# Pour_Over_1_Final.net
KiCad netlist of a schematic drawn in Altium Designer
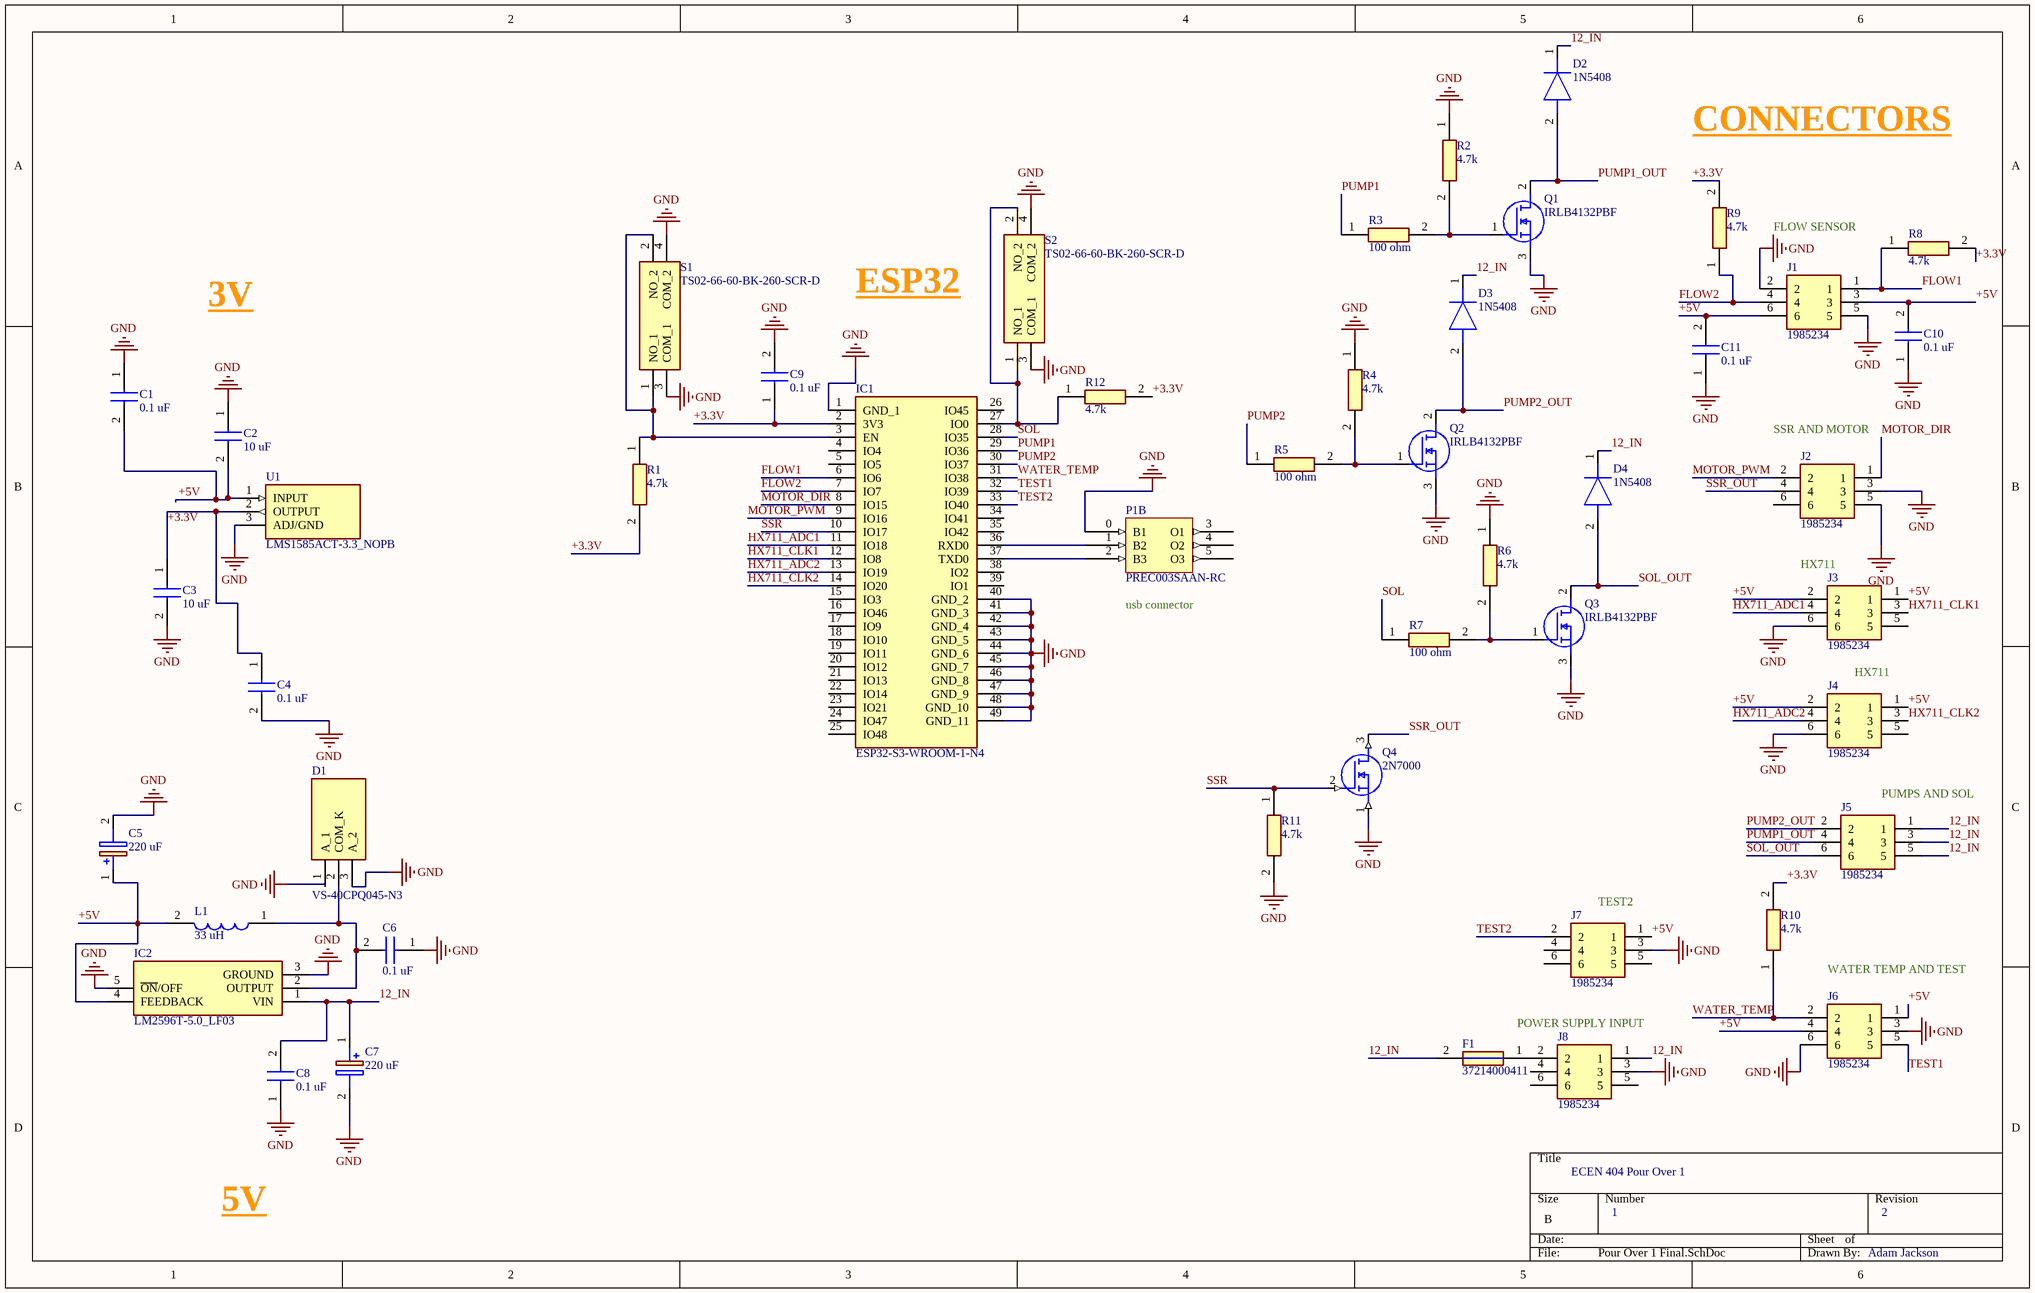
[diagram p0: Pour Over 1 Final.SchDoc]

(export (version "E")
  (design (tool "Eeschema 10.0.6"))
  (components
    (comp (ref "C1")
      (value "0.1 uF")
      (footprint "SamacSys:K104K10X7RF5TL2")
      (description "Capacitor")
      (fields
        (field (name "MANUFACTURER_PART_NUMBER") "K104K10X7RF5TL2")
        (field (name "MOUSER PART NUMBER") "594-K104K10X7RF5TL2")
      )
      (libsource (lib "*") (part "K104K10X7RF5TL2"))
    )
    (comp (ref "C2")
      (value "10 uF")
      (footprint "SamacSys:FG16")
      (description "Capacitor")
      (fields
        (field (name "MANUFACTURER_PART_NUMBER") "FG16X7R1E106KRT06")
        (field (name "MOUSER PART NUMBER") "810-FG16X7R1E106KRT6")
      )
      (libsource (lib "*") (part "FG16X7R1E106KRT06"))
    )
    (comp (ref "C3")
      (value "10 uF")
      (footprint "SamacSys:FG16")
      (description "Capacitor")
      (fields
        (field (name "MANUFACTURER_PART_NUMBER") "FG16X7R1E106KRT06")
        (field (name "MOUSER PART NUMBER") "810-FG16X7R1E106KRT6")
      )
      (libsource (lib "*") (part "FG16X7R1E106KRT06"))
    )
    (comp (ref "C4")
      (value "0.1 uF")
      (footprint "SamacSys:K104K10X7RF5TL2")
      (description "Capacitor")
      (fields
        (field (name "MANUFACTURER_PART_NUMBER") "K104K10X7RF5TL2")
        (field (name "MOUSER PART NUMBER") "594-K104K10X7RF5TL2")
      )
      (libsource (lib "*") (part "K104K10X7RF5TL2"))
    )
    (comp (ref "C5")
      (value "220 uF")
      (footprint "Footprints:EEHZT1E331UP")
      (description "Capacitor Polarised")
      (fields
        (field (name "MANUFACTURER_PART_NUMBER") "EEE-TP1C221AP")
        (field (name "MOUSER PART NUMBER") "667-EEE-TP1C221AP")
      )
      (libsource (lib "*") (part "EEE-TP1C221AP"))
    )
    (comp (ref "C6")
      (value "0.1 uF")
      (footprint "SamacSys:K104K10X7RF5TL2")
      (description "Capacitor")
      (fields
        (field (name "MANUFACTURER_PART_NUMBER") "K104K10X7RF5TL2")
        (field (name "MOUSER PART NUMBER") "594-K104K10X7RF5TL2")
      )
      (libsource (lib "*") (part "K104K10X7RF5TL2"))
    )
    (comp (ref "C7")
      (value "220 uF")
      (footprint "Footprints:EEHZT1E331UP")
      (description "Capacitor Polarised")
      (fields
        (field (name "MANUFACTURER_PART_NUMBER") "EEE-TP1C221AP")
        (field (name "MOUSER PART NUMBER") "667-EEE-TP1C221AP")
      )
      (libsource (lib "") (part "EEE-TP1C221AP_1"))
    )
    (comp (ref "C8")
      (value "0.1 uF")
      (footprint "SamacSys:K104K10X7RF5TL2")
      (description "Capacitor")
      (fields
        (field (name "MANUFACTURER_PART_NUMBER") "K104K10X7RF5TL2")
        (field (name "MOUSER PART NUMBER") "594-K104K10X7RF5TL2")
      )
      (libsource (lib "*") (part "K104K10X7RF5TL2"))
    )
    (comp (ref "C9")
      (value "0.1 uF")
      (footprint "SamacSys:K104K10X7RF5TL2")
      (description "Capacitor")
      (fields
        (field (name "MANUFACTURER_PART_NUMBER") "K104K10X7RF5TL2")
        (field (name "MOUSER PART NUMBER") "594-K104K10X7RF5TL2")
      )
      (libsource (lib "*") (part "K104K10X7RF5TL2"))
    )
    (comp (ref "C10")
      (value "0.1 uF")
      (footprint "SamacSys:K104K10X7RF5TL2")
      (description "Capacitor")
      (fields
        (field (name "MANUFACTURER_PART_NUMBER") "K104K10X7RF5TL2")
        (field (name "MOUSER PART NUMBER") "594-K104K10X7RF5TL2")
      )
      (libsource (lib "*") (part "K104K10X7RF5TL2"))
    )
    (comp (ref "C11")
      (value "0.1 uF")
      (footprint "SamacSys:K104K10X7RF5TL2")
      (description "Capacitor")
      (fields
        (field (name "MANUFACTURER_PART_NUMBER") "K104K10X7RF5TL2")
        (field (name "MOUSER PART NUMBER") "594-K104K10X7RF5TL2")
      )
      (libsource (lib "*") (part "K104K10X7RF5TL2"))
    )
    (comp (ref "D1")
      (value "VS-40CPQ045-N3")
      (footprint "Footprints:TO546P531X1558X2499-3P")
      (description "Diode")
      (fields (field (name "MOUSER PART NUMBER") "78-VS-40CPQ045-N3"))
      (libsource (lib "SamacSys") (part "VS-40CPQ045-N3"))
    )
    (comp (ref "D2")
      (value "1N5408")
      (footprint "SamacSys:DIOAD3020W130L900D530")
      (description "Diode")
      (libsource (lib "*") (part "1N5408"))
    )
    (comp (ref "D3")
      (value "1N5408")
      (footprint "SamacSys:DIOAD3020W130L900D530")
      (description "Diode")
      (libsource (lib "*") (part "1N5408"))
    )
    (comp (ref "D4")
      (value "1N5408")
      (footprint "SamacSys:DIOAD3020W130L900D530")
      (description "Diode")
      (libsource (lib "*") (part "1N5408"))
    )
    (comp (ref "F1")
      (value "37214000411")
      (footprint "SamacSys:37214000411")
      (description "Fuse")
      (fields (field (name "MOUSER PART NUMBER") "576-37214000411"))
      (libsource (lib "*") (part "37214000411"))
    )
    (comp (ref "IC1")
      (value "ESP32-S3-WROOM-1-N4")
      (footprint "Footprints:ESP32S3WROOM1N4")
      (description "Integrated Circuit")
      (fields (field (name "MOUSER PART NUMBER") "356-ESP32-S3WROOM1N4"))
      (libsource (lib "SamacSys") (part "ESP32-S3-WROOM-1-N4"))
    )
    (comp (ref "IC2")
      (value "LM2596T-5.0_LF03")
      (footprint "Footprints:TO170P470X1028X2142-5P")
      (description "Integrated Circuit")
      (fields
        (field (name "MANUFACTURER_PART_NUMBER") "LM2596T-5.0/LF03")
        (field (name "MOUSER PART NUMBER") "926-LM2596T-50/LF03")
      )
      (libsource (lib "Pour Over 1") (part "LM2596T-5.0_LF03"))
    )
    (comp (ref "J1")
      (value "1985234")
      (footprint "SamacSys:1985234")
      (description "Connector")
      (fields (field (name "MOUSER PART NUMBER") "651-1985234"))
      (libsource (lib "*") (part "1985234"))
    )
    (comp (ref "J2")
      (value "1985234")
      (footprint "SamacSys:1985234")
      (description "Connector")
      (fields (field (name "MOUSER PART NUMBER") "651-1985234"))
      (libsource (lib "*") (part "1985234"))
    )
    (comp (ref "J3")
      (value "1985234")
      (footprint "SamacSys:1985234")
      (description "Connector")
      (fields (field (name "MOUSER PART NUMBER") "651-1985234"))
      (libsource (lib "*") (part "1985234"))
    )
    (comp (ref "J4")
      (value "1985234")
      (footprint "SamacSys:1985234")
      (description "Connector")
      (fields (field (name "MOUSER PART NUMBER") "651-1985234"))
      (libsource (lib "*") (part "1985234"))
    )
    (comp (ref "J5")
      (value "1985234")
      (footprint "SamacSys:1985234")
      (description "Connector")
      (fields (field (name "MOUSER PART NUMBER") "651-1985234"))
      (libsource (lib "*") (part "1985234"))
    )
    (comp (ref "J6")
      (value "1985234")
      (footprint "SamacSys:1985234")
      (description "Connector")
      (fields (field (name "MOUSER PART NUMBER") "651-1985234"))
      (libsource (lib "*") (part "1985234"))
    )
    (comp (ref "J7")
      (value "1985234")
      (footprint "SamacSys:1985234")
      (description "Connector")
      (fields (field (name "MOUSER PART NUMBER") "651-1985234"))
      (libsource (lib "*") (part "1985234"))
    )
    (comp (ref "J8")
      (value "1985234")
      (footprint "SamacSys:1985234")
      (description "Connector")
      (fields (field (name "MOUSER PART NUMBER") "651-1985234"))
      (libsource (lib "*") (part "1985234"))
    )
    (comp (ref "L1")
      (value "33 uH")
      (footprint "Footprints:INDPM8680X400N")
      (description "Inductor")
      (fields (field (name "MANUFACTURER_PART_NUMBER") "F1F2-0804-330M"))
      (libsource (lib "Pour Over 1") (part "F1F2-0804-330M"))
    )
    (comp (ref "P1")
      (value "PREC003SAAN-RC")
      (footprint "CONNECTOR")
      (description "ESP32 USB Connector")
      (libsource (lib "Pour Over 1") (part "PREC003SAAN-RC"))
    )
    (comp (ref "Q1")
      (value "IRLB4132PBF")
      (footprint "SamacSys:TO254P483X1016X1994-3P")
      (description "MOSFET (N-Channel)")
      (fields (field (name "MOUSER PART NUMBER") "942-IRLB4132PBF"))
      (libsource (lib "*") (part "IRLB4132PBF"))
    )
    (comp (ref "Q2")
      (value "IRLB4132PBF")
      (footprint "SamacSys:TO254P483X1016X1994-3P")
      (description "MOSFET (N-Channel)")
      (fields (field (name "MOUSER PART NUMBER") "942-IRLB4132PBF"))
      (libsource (lib "*") (part "IRLB4132PBF"))
    )
    (comp (ref "Q3")
      (value "IRLB4132PBF")
      (footprint "SamacSys:TO254P483X1016X1994-3P")
      (description "MOSFET (N-Channel)")
      (fields (field (name "MOUSER PART NUMBER") "942-IRLB4132PBF"))
      (libsource (lib "*") (part "IRLB4132PBF"))
    )
    (comp (ref "Q4")
      (value "2N7000")
      (footprint "SamacSys:TO-92_(TO-226)")
      (description "MOSFET (N-Channel)")
      (fields (field (name "MOUSER PART NUMBER") "512-2N7000"))
      (libsource (lib "*") (part "2N7000"))
    )
    (comp (ref "R1")
      (value "4.7k")
      (footprint "SamacSys:RESAD1526W69L610D229")
      (description "Resistor")
      (fields (field (name "MANUFACTURER_PART_NUMBER") "RN55E4701BRE6"))
      (libsource (lib "*") (part "RN55E4701BRE6"))
    )
    (comp (ref "R2")
      (value "4.7k")
      (footprint "SamacSys:RESAD1526W69L610D229")
      (description "Resistor")
      (fields (field (name "MANUFACTURER_PART_NUMBER") "RN55E4701BRE6"))
      (libsource (lib "*") (part "RN55E4701BRE6"))
    )
    (comp (ref "R3")
      (value "100 ohm")
      (footprint "SamacSys:RESAD1590W70L630D240")
      (description "Resistor")
      (fields
        (field (name "MANUFACTURER_PART_NUMBER") "MFP-25BRD52-100R")
        (field (name "MOUSER PART NUMBER") "603-MFP-25BRD52-100R")
      )
      (libsource (lib "*") (part "MFP-25BRD52-100R"))
    )
    (comp (ref "R4")
      (value "4.7k")
      (footprint "SamacSys:RESAD1526W69L610D229")
      (description "Resistor")
      (fields (field (name "MANUFACTURER_PART_NUMBER") "RN55E4701BRE6"))
      (libsource (lib "*") (part "RN55E4701BRE6"))
    )
    (comp (ref "R5")
      (value "100 ohm")
      (footprint "SamacSys:RESAD1590W70L630D240")
      (description "Resistor")
      (fields
        (field (name "MANUFACTURER_PART_NUMBER") "MFP-25BRD52-100R")
        (field (name "MOUSER PART NUMBER") "603-MFP-25BRD52-100R")
      )
      (libsource (lib "*") (part "MFP-25BRD52-100R"))
    )
    (comp (ref "R6")
      (value "4.7k")
      (footprint "SamacSys:RESAD1526W69L610D229")
      (description "Resistor")
      (fields (field (name "MANUFACTURER_PART_NUMBER") "RN55E4701BRE6"))
      (libsource (lib "*") (part "RN55E4701BRE6"))
    )
    (comp (ref "R7")
      (value "100 ohm")
      (footprint "SamacSys:RESAD1590W70L630D240")
      (description "Resistor")
      (fields
        (field (name "MANUFACTURER_PART_NUMBER") "MFP-25BRD52-100R")
        (field (name "MOUSER PART NUMBER") "603-MFP-25BRD52-100R")
      )
      (libsource (lib "*") (part "MFP-25BRD52-100R"))
    )
    (comp (ref "R8")
      (value "4.7k")
      (footprint "SamacSys:RESAD1526W69L610D229")
      (description "Resistor")
      (fields (field (name "MANUFACTURER_PART_NUMBER") "RN55E4701BRE6"))
      (libsource (lib "") (part "RN55E4701BRE6_2"))
    )
    (comp (ref "R9")
      (value "4.7k")
      (footprint "SamacSys:RESAD1526W69L610D229")
      (description "Resistor")
      (fields (field (name "MANUFACTURER_PART_NUMBER") "RN55E4701BRE6"))
      (libsource (lib "") (part "RN55E4701BRE6_1"))
    )
    (comp (ref "R10")
      (value "4.7k")
      (footprint "SamacSys:RESAD1526W69L610D229")
      (description "Resistor")
      (fields (field (name "MANUFACTURER_PART_NUMBER") "RN55E4701BRE6"))
      (libsource (lib "") (part "RN55E4701BRE6_1"))
    )
    (comp (ref "R11")
      (value "4.7k")
      (footprint "SamacSys:RESAD1526W69L610D229")
      (description "Resistor")
      (fields (field (name "MANUFACTURER_PART_NUMBER") "RN55E4701BRE6"))
      (libsource (lib "*") (part "RN55E4701BRE6"))
    )
    (comp (ref "R12")
      (value "4.7k")
      (footprint "SamacSys:RESAD1526W69L610D229")
      (description "Resistor")
      (fields (field (name "MANUFACTURER_PART_NUMBER") "RN55E4701BRE6"))
      (libsource (lib "") (part "RN55E4701BRE6_2"))
    )
    (comp (ref "S1")
      (value "TS02-66-60-BK-260-SCR-D")
      (footprint "SamacSys:TS026660BK260SCRD")
      (description "Switch")
      (fields (field (name "MOUSER PART NUMBER") "179-TS026660BK260SCR"))
      (libsource (lib "*") (part "TS02-66-60-BK-260-SCR-D"))
    )
    (comp (ref "S2")
      (value "TS02-66-60-BK-260-SCR-D")
      (footprint "SamacSys:TS026660BK260SCRD")
      (description "Switch")
      (fields (field (name "MOUSER PART NUMBER") "179-TS026660BK260SCR"))
      (libsource (lib "*") (part "TS02-66-60-BK-260-SCR-D"))
    )
    (comp (ref "U1")
      (value "LMS1585ACT-3.3_NOPB")
      (footprint "Footprints:TO254P470X1028X1955-3P")
      (description "Undefined or Miscellaneous")
      (fields
        (field (name "MANUFACTURER_PART_NUMBER") "LMS1585ACT-3.3/NOPB")
        (field (name "MOUSER PART NUMBER") "926-LMS1585ACT33NOPB")
      )
      (libsource (lib "Pour Over 1") (part "LMS1585ACT-3.3_NOPB"))
    )
  )
  (nets
    (net (code "1") (name "/+3.3V") (class "Default")
      (node (ref "C3") (pin "1") (pinfunction "1_1") (pintype "passive"))
      (node (ref "C4") (pin "1") (pinfunction "1_1") (pintype "passive"))
      (node (ref "C9") (pin "1") (pinfunction "1_1") (pintype "passive"))
      (node (ref "IC1") (pin "2") (pinfunction "3V3_2") (pintype "passive"))
      (node (ref "R1") (pin "2") (pinfunction "2_2") (pintype "passive"))
      (node (ref "R10") (pin "2") (pinfunction "2_2") (pintype "passive"))
      (node (ref "R12") (pin "2") (pinfunction "2_2") (pintype "passive"))
      (node (ref "R8") (pin "2") (pinfunction "2_2") (pintype "passive"))
      (node (ref "R9") (pin "2") (pinfunction "2_2") (pintype "passive"))
      (node (ref "U1") (pin "2") (pinfunction "OUTPUT_2") (pintype "output"))
    )
    (net (code "2") (name "/+5V") (class "Default")
      (node (ref "C1") (pin "2") (pinfunction "2_2") (pintype "passive"))
      (node (ref "C10") (pin "2") (pinfunction "2_2") (pintype "passive"))
      (node (ref "C11") (pin "2") (pinfunction "2_2") (pintype "passive"))
      (node (ref "C2") (pin "2") (pinfunction "2_2") (pintype "passive"))
      (node (ref "C5") (pin "1") (pinfunction "+_1") (pintype "passive"))
      (node (ref "IC2") (pin "4") (pinfunction "FEEDBACK_4") (pintype "passive"))
      (node (ref "J1") (pin "3") (pinfunction "3_3") (pintype "passive"))
      (node (ref "J1") (pin "6") (pinfunction "6_6") (pintype "passive"))
      (node (ref "J3") (pin "1") (pinfunction "1_1") (pintype "passive"))
      (node (ref "J3") (pin "2") (pinfunction "2_2") (pintype "passive"))
      (node (ref "J4") (pin "1") (pinfunction "1_1") (pintype "passive"))
      (node (ref "J4") (pin "2") (pinfunction "2_2") (pintype "passive"))
      (node (ref "J6") (pin "1") (pinfunction "1_1") (pintype "passive"))
      (node (ref "J6") (pin "4") (pinfunction "4_4") (pintype "passive"))
      (node (ref "J7") (pin "1") (pinfunction "1_1") (pintype "passive"))
      (node (ref "L1") (pin "2") (pinfunction "2_2") (pintype "passive"))
      (node (ref "U1") (pin "1") (pinfunction "INPUT_1") (pintype "input"))
    )
    (net (code "3") (name "/12_IN") (class "Default")
      (node (ref "C7") (pin "1") (pinfunction "+_1") (pintype "passive"))
      (node (ref "C8") (pin "2") (pinfunction "2_2") (pintype "passive"))
      (node (ref "D2") (pin "1") (pinfunction "K_1") (pintype "passive"))
      (node (ref "D3") (pin "1") (pinfunction "K_1") (pintype "passive"))
      (node (ref "D4") (pin "1") (pinfunction "K_1") (pintype "passive"))
      (node (ref "F1") (pin "2") (pinfunction "2_2") (pintype "passive"))
      (node (ref "IC2") (pin "1") (pinfunction "VIN_1") (pintype "passive"))
      (node (ref "J5") (pin "1") (pinfunction "1_1") (pintype "passive"))
      (node (ref "J5") (pin "3") (pinfunction "3_3") (pintype "passive"))
      (node (ref "J5") (pin "5") (pinfunction "5_5") (pintype "passive"))
      (node (ref "J8") (pin "1") (pinfunction "1_1") (pintype "passive"))
    )
    (net (code "4") (name "/FLOW1") (class "Default")
      (node (ref "IC1") (pin "6") (pinfunction "IO6_6") (pintype "passive"))
      (node (ref "J1") (pin "1") (pinfunction "1_1") (pintype "passive"))
      (node (ref "R8") (pin "1") (pinfunction "1_1") (pintype "passive"))
    )
    (net (code "5") (name "/FLOW2") (class "Default")
      (node (ref "IC1") (pin "7") (pinfunction "IO7_7") (pintype "passive"))
      (node (ref "J1") (pin "4") (pinfunction "4_4") (pintype "passive"))
      (node (ref "R9") (pin "1") (pinfunction "1_1") (pintype "passive"))
    )
    (net (code "6") (name "/HX711_ADC1") (class "Default")
      (node (ref "IC1") (pin "11") (pinfunction "IO18_11") (pintype "passive"))
      (node (ref "J3") (pin "4") (pinfunction "4_4") (pintype "passive"))
    )
    (net (code "7") (name "/HX711_ADC2") (class "Default")
      (node (ref "IC1") (pin "13") (pinfunction "IO19_13") (pintype "passive"))
      (node (ref "J4") (pin "4") (pinfunction "4_4") (pintype "passive"))
    )
    (net (code "8") (name "/HX711_CLK1") (class "Default")
      (node (ref "IC1") (pin "12") (pinfunction "IO8_12") (pintype "passive"))
      (node (ref "J3") (pin "3") (pinfunction "3_3") (pintype "passive"))
    )
    (net (code "9") (name "/HX711_CLK2") (class "Default")
      (node (ref "IC1") (pin "14") (pinfunction "IO20_14") (pintype "passive"))
      (node (ref "J4") (pin "3") (pinfunction "3_3") (pintype "passive"))
    )
    (net (code "10") (name "/MOTOR_DIR") (class "Default")
      (node (ref "IC1") (pin "8") (pinfunction "IO15_8") (pintype "passive"))
      (node (ref "J2") (pin "1") (pinfunction "1_1") (pintype "passive"))
    )
    (net (code "11") (name "/MOTOR_PWM") (class "Default")
      (node (ref "IC1") (pin "9") (pinfunction "IO16_9") (pintype "passive"))
      (node (ref "J2") (pin "2") (pinfunction "2_2") (pintype "passive"))
    )
    (net (code "12") (name "/PUMP1") (class "Default")
      (node (ref "IC1") (pin "29") (pinfunction "IO36_29") (pintype "passive"))
      (node (ref "R3") (pin "1") (pinfunction "1_1") (pintype "passive"))
    )
    (net (code "13") (name "/PUMP1_OUT") (class "Default")
      (node (ref "D2") (pin "2") (pinfunction "A_2") (pintype "passive"))
      (node (ref "J5") (pin "4") (pinfunction "4_4") (pintype "passive"))
      (node (ref "Q1") (pin "2") (pinfunction "D_2") (pintype "passive"))
    )
    (net (code "14") (name "/PUMP2") (class "Default")
      (node (ref "IC1") (pin "30") (pinfunction "IO37_30") (pintype "passive"))
      (node (ref "R5") (pin "1") (pinfunction "1_1") (pintype "passive"))
    )
    (net (code "15") (name "/PUMP2_OUT") (class "Default")
      (node (ref "D3") (pin "2") (pinfunction "A_2") (pintype "passive"))
      (node (ref "J5") (pin "2") (pinfunction "2_2") (pintype "passive"))
      (node (ref "Q2") (pin "2") (pinfunction "D_2") (pintype "passive"))
    )
    (net (code "16") (name "/SOL") (class "Default")
      (node (ref "IC1") (pin "28") (pinfunction "IO35_28") (pintype "passive"))
      (node (ref "R7") (pin "1") (pinfunction "1_1") (pintype "passive"))
    )
    (net (code "17") (name "/SOL_OUT") (class "Default")
      (node (ref "D4") (pin "2") (pinfunction "A_2") (pintype "passive"))
      (node (ref "J5") (pin "6") (pinfunction "6_6") (pintype "passive"))
      (node (ref "Q3") (pin "2") (pinfunction "D_2") (pintype "passive"))
    )
    (net (code "18") (name "/SSR") (class "Default")
      (node (ref "IC1") (pin "10") (pinfunction "IO17_10") (pintype "passive"))
      (node (ref "Q4") (pin "2") (pinfunction "G_2") (pintype "input"))
      (node (ref "R11") (pin "1") (pinfunction "1_1") (pintype "passive"))
    )
    (net (code "19") (name "/SSR_OUT") (class "Default")
      (node (ref "J2") (pin "4") (pinfunction "4_4") (pintype "passive"))
      (node (ref "Q4") (pin "3") (pinfunction "D_3") (pintype "output"))
    )
    (net (code "20") (name "/TEST1") (class "Default")
      (node (ref "IC1") (pin "32") (pinfunction "IO39_32") (pintype "passive"))
      (node (ref "J6") (pin "5") (pinfunction "5_5") (pintype "passive"))
    )
    (net (code "21") (name "/TEST2") (class "Default")
      (node (ref "IC1") (pin "33") (pinfunction "IO40_33") (pintype "passive"))
      (node (ref "J7") (pin "2") (pinfunction "2_2") (pintype "passive"))
    )
    (net (code "22") (name "/WATER_TEMP") (class "Default")
      (node (ref "IC1") (pin "31") (pinfunction "IO38_31") (pintype "passive"))
      (node (ref "J6") (pin "2") (pinfunction "2_2") (pintype "passive"))
      (node (ref "R10") (pin "1") (pinfunction "1_1") (pintype "passive"))
    )
    (net (code "23") (name "GND") (class "Default")
      (node (ref "C1") (pin "1") (pinfunction "1_1") (pintype "passive"))
      (node (ref "C10") (pin "1") (pinfunction "1_1") (pintype "passive"))
      (node (ref "C11") (pin "1") (pinfunction "1_1") (pintype "passive"))
      (node (ref "C2") (pin "1") (pinfunction "1_1") (pintype "passive"))
      (node (ref "C3") (pin "2") (pinfunction "2_2") (pintype "passive"))
      (node (ref "C4") (pin "2") (pinfunction "2_2") (pintype "passive"))
      (node (ref "C5") (pin "2") (pinfunction "-_2") (pintype "passive"))
      (node (ref "C6") (pin "1") (pinfunction "1_1") (pintype "passive"))
      (node (ref "C7") (pin "2") (pinfunction "-_2") (pintype "passive"))
      (node (ref "C8") (pin "1") (pinfunction "1_1") (pintype "passive"))
      (node (ref "C9") (pin "2") (pinfunction "2_2") (pintype "passive"))
      (node (ref "D1") (pin "1") (pinfunction "A_1_1") (pintype "passive"))
      (node (ref "D1") (pin "3") (pinfunction "A_2_3") (pintype "passive"))
      (node (ref "IC1") (pin "1") (pinfunction "GND_1_1") (pintype "passive"))
      (node (ref "IC1") (pin "40") (pinfunction "GND_2_40") (pintype "passive"))
      (node (ref "IC1") (pin "41") (pinfunction "GND_3_41") (pintype "passive"))
      (node (ref "IC1") (pin "42") (pinfunction "GND_4_42") (pintype "passive"))
      (node (ref "IC1") (pin "43") (pinfunction "GND_5_43") (pintype "passive"))
      (node (ref "IC1") (pin "44") (pinfunction "GND_6_44") (pintype "passive"))
      (node (ref "IC1") (pin "45") (pinfunction "GND_7_45") (pintype "passive"))
      (node (ref "IC1") (pin "46") (pinfunction "GND_8_46") (pintype "passive"))
      (node (ref "IC1") (pin "47") (pinfunction "GND_9_47") (pintype "passive"))
      (node (ref "IC1") (pin "48") (pinfunction "GND_10_48") (pintype "passive"))
      (node (ref "IC1") (pin "49") (pinfunction "GND_11_49") (pintype "passive"))
      (node (ref "IC2") (pin "3") (pinfunction "GROUND_3") (pintype "passive"))
      (node (ref "IC2") (pin "5") (pinfunction "~{ON}/OFF_5") (pintype "passive"))
      (node (ref "J1") (pin "2") (pinfunction "2_2") (pintype "passive"))
      (node (ref "J1") (pin "5") (pinfunction "5_5") (pintype "passive"))
      (node (ref "J2") (pin "3") (pinfunction "3_3") (pintype "passive"))
      (node (ref "J2") (pin "5") (pinfunction "5_5") (pintype "passive"))
      (node (ref "J3") (pin "6") (pinfunction "6_6") (pintype "passive"))
      (node (ref "J4") (pin "6") (pinfunction "6_6") (pintype "passive"))
      (node (ref "J6") (pin "3") (pinfunction "3_3") (pintype "passive"))
      (node (ref "J6") (pin "6") (pinfunction "6_6") (pintype "passive"))
      (node (ref "J7") (pin "3") (pinfunction "3_3") (pintype "passive"))
      (node (ref "J8") (pin "3") (pinfunction "3_3") (pintype "passive"))
      (node (ref "P1") (pin "0") (pinfunction "B1_0") (pintype "input"))
      (node (ref "Q1") (pin "3") (pinfunction "S_3") (pintype "passive"))
      (node (ref "Q2") (pin "3") (pinfunction "S_3") (pintype "passive"))
      (node (ref "Q3") (pin "3") (pinfunction "S_3") (pintype "passive"))
      (node (ref "Q4") (pin "1") (pinfunction "S_1") (pintype "input"))
      (node (ref "R11") (pin "2") (pinfunction "2_2") (pintype "passive"))
      (node (ref "R2") (pin "1") (pinfunction "1_1") (pintype "passive"))
      (node (ref "R4") (pin "1") (pinfunction "1_1") (pintype "passive"))
      (node (ref "R6") (pin "1") (pinfunction "1_1") (pintype "passive"))
      (node (ref "S1") (pin "3") (pinfunction "COM_1_3") (pintype "passive"))
      (node (ref "S1") (pin "4") (pinfunction "COM_2_4") (pintype "passive"))
      (node (ref "S2") (pin "3") (pinfunction "COM_1_3") (pintype "passive"))
      (node (ref "S2") (pin "4") (pinfunction "COM_2_4") (pintype "passive"))
      (node (ref "U1") (pin "3") (pinfunction "ADJ/GND_3") (pintype "power_in"))
    )
    (net (code "24") (name "Net-(D1-COM_K)") (class "Default")
      (node (ref "C6") (pin "2") (pinfunction "2_2") (pintype "passive"))
      (node (ref "D1") (pin "2") (pinfunction "COM_K_2") (pintype "passive"))
      (node (ref "IC2") (pin "2") (pinfunction "OUTPUT_2") (pintype "passive"))
      (node (ref "L1") (pin "1") (pinfunction "1_1") (pintype "passive"))
    )
    (net (code "25") (name "Net-(F1-Pad1)") (class "Default")
      (node (ref "F1") (pin "1") (pinfunction "1_1") (pintype "passive"))
      (node (ref "J8") (pin "2") (pinfunction "2_2") (pintype "passive"))
    )
    (net (code "26") (name "Net-(IC1-EN)") (class "Default")
      (node (ref "IC1") (pin "3") (pinfunction "EN_3") (pintype "passive"))
      (node (ref "R1") (pin "1") (pinfunction "1_1") (pintype "passive"))
      (node (ref "S1") (pin "1") (pinfunction "NO_1_1") (pintype "passive"))
      (node (ref "S1") (pin "2") (pinfunction "NO_2_2") (pintype "passive"))
    )
    (net (code "27") (name "Net-(IC1-IO0)") (class "Default")
      (node (ref "IC1") (pin "27") (pinfunction "IO0_27") (pintype "passive"))
      (node (ref "R12") (pin "1") (pinfunction "1_1") (pintype "passive"))
      (node (ref "S2") (pin "1") (pinfunction "NO_1_1") (pintype "passive"))
      (node (ref "S2") (pin "2") (pinfunction "NO_2_2") (pintype "passive"))
    )
    (net (code "28") (name "Net-(IC1-RXD0)") (class "Default")
      (node (ref "IC1") (pin "36") (pinfunction "RXD0_36") (pintype "passive"))
      (node (ref "P1") (pin "1") (pinfunction "B2_1") (pintype "input"))
    )
    (net (code "29") (name "Net-(IC1-TXD0)") (class "Default")
      (node (ref "IC1") (pin "37") (pinfunction "TXD0_37") (pintype "passive"))
      (node (ref "P1") (pin "2") (pinfunction "B3_2") (pintype "input"))
    )
    (net (code "30") (name "Net-(Q1-G)") (class "Default")
      (node (ref "Q1") (pin "1") (pinfunction "G_1") (pintype "passive"))
      (node (ref "R2") (pin "2") (pinfunction "2_2") (pintype "passive"))
      (node (ref "R3") (pin "2") (pinfunction "2_2") (pintype "passive"))
    )
    (net (code "31") (name "Net-(Q2-G)") (class "Default")
      (node (ref "Q2") (pin "1") (pinfunction "G_1") (pintype "passive"))
      (node (ref "R4") (pin "2") (pinfunction "2_2") (pintype "passive"))
      (node (ref "R5") (pin "2") (pinfunction "2_2") (pintype "passive"))
    )
    (net (code "32") (name "Net-(Q3-G)") (class "Default")
      (node (ref "Q3") (pin "1") (pinfunction "G_1") (pintype "passive"))
      (node (ref "R6") (pin "2") (pinfunction "2_2") (pintype "passive"))
      (node (ref "R7") (pin "2") (pinfunction "2_2") (pintype "passive"))
    )
    (net (code "33") (name "unconnected-(IC1-IO1-Pad39)") (class "Default")
      (node (ref "IC1") (pin "39") (pinfunction "IO1_39") (pintype "passive"))
    )
    (net (code "34") (name "unconnected-(IC1-IO2-Pad38)") (class "Default")
      (node (ref "IC1") (pin "38") (pinfunction "IO2_38") (pintype "passive"))
    )
    (net (code "35") (name "unconnected-(IC1-IO3-Pad15)") (class "Default")
      (node (ref "IC1") (pin "15") (pinfunction "IO3_15") (pintype "passive"))
    )
    (net (code "36") (name "unconnected-(IC1-IO4-Pad4)") (class "Default")
      (node (ref "IC1") (pin "4") (pinfunction "IO4_4") (pintype "passive"))
    )
    (net (code "37") (name "unconnected-(IC1-IO5-Pad5)") (class "Default")
      (node (ref "IC1") (pin "5") (pinfunction "IO5_5") (pintype "passive"))
    )
    (net (code "38") (name "unconnected-(IC1-IO9-Pad17)") (class "Default")
      (node (ref "IC1") (pin "17") (pinfunction "IO9_17") (pintype "passive"))
    )
    (net (code "39") (name "unconnected-(IC1-IO10-Pad18)") (class "Default")
      (node (ref "IC1") (pin "18") (pinfunction "IO10_18") (pintype "passive"))
    )
    (net (code "40") (name "unconnected-(IC1-IO11-Pad19)") (class "Default")
      (node (ref "IC1") (pin "19") (pinfunction "IO11_19") (pintype "passive"))
    )
    (net (code "41") (name "unconnected-(IC1-IO12-Pad20)") (class "Default")
      (node (ref "IC1") (pin "20") (pinfunction "IO12_20") (pintype "passive"))
    )
    (net (code "42") (name "unconnected-(IC1-IO13-Pad21)") (class "Default")
      (node (ref "IC1") (pin "21") (pinfunction "IO13_21") (pintype "passive"))
    )
    (net (code "43") (name "unconnected-(IC1-IO14-Pad22)") (class "Default")
      (node (ref "IC1") (pin "22") (pinfunction "IO14_22") (pintype "passive"))
    )
    (net (code "44") (name "unconnected-(IC1-IO21-Pad23)") (class "Default")
      (node (ref "IC1") (pin "23") (pinfunction "IO21_23") (pintype "passive"))
    )
    (net (code "45") (name "unconnected-(IC1-IO41-Pad34)") (class "Default")
      (node (ref "IC1") (pin "34") (pinfunction "IO41_34") (pintype "passive"))
    )
    (net (code "46") (name "unconnected-(IC1-IO42-Pad35)") (class "Default")
      (node (ref "IC1") (pin "35") (pinfunction "IO42_35") (pintype "passive"))
    )
    (net (code "47") (name "unconnected-(IC1-IO45-Pad26)") (class "Default")
      (node (ref "IC1") (pin "26") (pinfunction "IO45_26") (pintype "passive"))
    )
    (net (code "48") (name "unconnected-(IC1-IO46-Pad16)") (class "Default")
      (node (ref "IC1") (pin "16") (pinfunction "IO46_16") (pintype "passive"))
    )
    (net (code "49") (name "unconnected-(IC1-IO47-Pad24)") (class "Default")
      (node (ref "IC1") (pin "24") (pinfunction "IO47_24") (pintype "passive"))
    )
    (net (code "50") (name "unconnected-(IC1-IO48-Pad25)") (class "Default")
      (node (ref "IC1") (pin "25") (pinfunction "IO48_25") (pintype "passive"))
    )
    (net (code "51") (name "unconnected-(J2-Pad6)") (class "Default")
      (node (ref "J2") (pin "6") (pinfunction "6_6") (pintype "passive"))
    )
    (net (code "52") (name "unconnected-(J3-Pad5)") (class "Default")
      (node (ref "J3") (pin "5") (pinfunction "5_5") (pintype "passive"))
    )
    (net (code "53") (name "unconnected-(J4-Pad5)") (class "Default")
      (node (ref "J4") (pin "5") (pinfunction "5_5") (pintype "passive"))
    )
    (net (code "54") (name "unconnected-(J7-Pad4)") (class "Default")
      (node (ref "J7") (pin "4") (pinfunction "4_4") (pintype "passive"))
    )
    (net (code "55") (name "unconnected-(J7-Pad5)") (class "Default")
      (node (ref "J7") (pin "5") (pinfunction "5_5") (pintype "passive"))
    )
    (net (code "56") (name "unconnected-(J7-Pad6)") (class "Default")
      (node (ref "J7") (pin "6") (pinfunction "6_6") (pintype "passive"))
    )
    (net (code "57") (name "unconnected-(J8-Pad4)") (class "Default")
      (node (ref "J8") (pin "4") (pinfunction "4_4") (pintype "passive"))
    )
    (net (code "58") (name "unconnected-(J8-Pad5)") (class "Default")
      (node (ref "J8") (pin "5") (pinfunction "5_5") (pintype "passive"))
    )
    (net (code "59") (name "unconnected-(J8-Pad6)") (class "Default")
      (node (ref "J8") (pin "6") (pinfunction "6_6") (pintype "passive"))
    )
    (net (code "60") (name "unconnected-(P1B-O1-Pad3)") (class "Default")
      (node (ref "P1") (pin "3") (pinfunction "O1_3") (pintype "output"))
    )
    (net (code "61") (name "unconnected-(P1B-O2-Pad4)") (class "Default")
      (node (ref "P1") (pin "4") (pinfunction "O2_4") (pintype "output"))
    )
    (net (code "62") (name "unconnected-(P1B-O3-Pad5)") (class "Default")
      (node (ref "P1") (pin "5") (pinfunction "O3_5") (pintype "output"))
    )
  )
)
